# Half-H_stage.net
KiCad netlist of a schematic drawn in Altium Designer
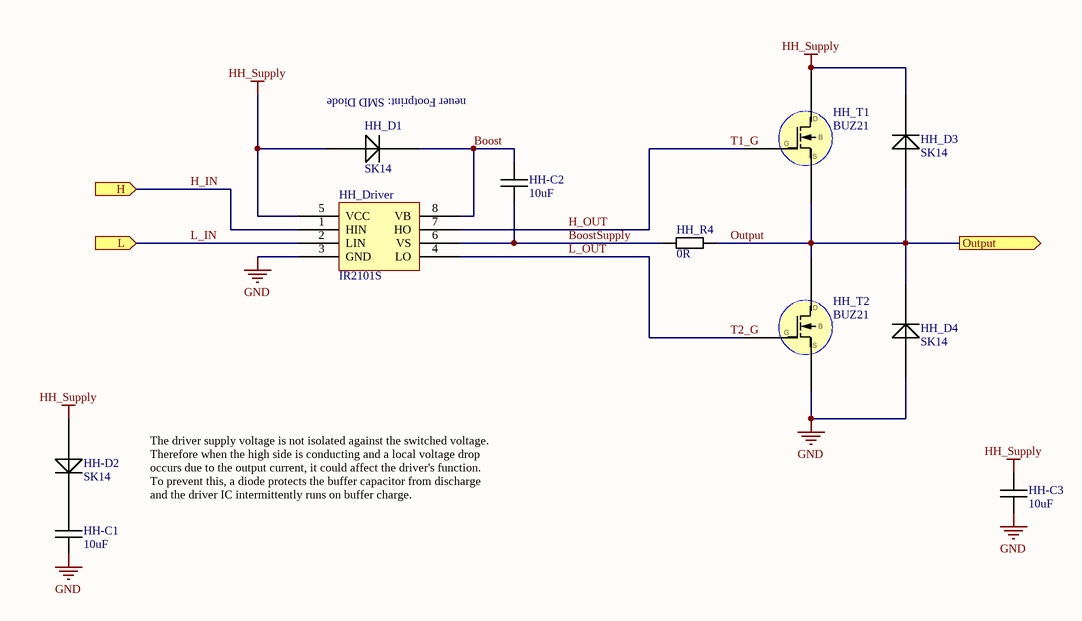
[diagram p0: Half-H stage.SchDoc]

(export (version "E")
  (design (tool "Eeschema 10.0.6"))
  (components
    (comp (ref "HH-C1")
      (value "10uF")
      (footprint "C 0805 / 2012")
      (libsource (lib "Standard") (part "Capacitor"))
    )
    (comp (ref "HH-C2")
      (value "10uF")
      (footprint "C 0805 / 2012")
      (libsource (lib "Standard") (part "Capacitor"))
    )
    (comp (ref "HH-C3")
      (value "10uF")
      (footprint "Header 1x2+1 1.0mm")
      (libsource (lib "Standard") (part "Capacitor"))
    )
    (comp (ref "HH-D2") (value "SK14") (footprint "SC-90") (libsource (lib "Standard") (part "Diode")))
    (comp (ref "HH_D1") (value "SK14") (footprint "SC-90") (libsource (lib "Standard") (part "Diode")))
    (comp (ref "HH_D3") (value "SK14") (footprint "SC-90") (libsource (lib "Standard") (part "Diode")))
    (comp (ref "HH_D4") (value "SK14") (footprint "SC-90") (libsource (lib "Standard") (part "Diode")))
    (comp (ref "HH_Driver")
      (value "IR2101S")
      (footprint "SOIC-8")
      (description "High and Low Side Driver")
      (libsource (lib "ICs") (part "IR21xx"))
    )
    (comp (ref "HH_R4")
      (value "0R")
      (footprint "R 0805 / 2012 wide")
      (libsource (lib "Standard") (part "Resistor"))
    )
    (comp (ref "HH_T1")
      (value "BUZ21")
      (footprint "TO-220 AB")
      (description "Enhancement Type")
      (libsource (lib "ICs") (part "FET N-Channel"))
    )
    (comp (ref "HH_T2")
      (value "BUZ21")
      (footprint "TO-220 AB")
      (description "Enhancement Type")
      (libsource (lib "ICs") (part "FET N-Channel"))
    )
  )
  (nets
    (net (code "1") (name "/Boost") (class "Default")
      (node (ref "HH-C2") (pin "1") (pinfunction "1_1") (pintype "passive"))
      (node (ref "HH_D1") (pin "1") (pinfunction "1_1") (pintype "passive"))
      (node (ref "HH_Driver") (pin "8") (pinfunction "VB_8") (pintype "passive"))
    )
    (net (code "2") (name "/BoostSupply") (class "Default")
      (node (ref "HH-C2") (pin "2") (pinfunction "1_2") (pintype "passive"))
      (node (ref "HH_Driver") (pin "6") (pinfunction "VS_6") (pintype "passive"))
      (node (ref "HH_R4") (pin "1") (pinfunction "1_1") (pintype "passive"))
    )
    (net (code "3") (name "/H_IN") (class "Default")
      (node (ref "HH_Driver") (pin "1") (pinfunction "HIN_1") (pintype "passive"))
    )
    (net (code "4") (name "/H_OUT") (class "Default")
      (node (ref "HH_Driver") (pin "7") (pinfunction "HO_7") (pintype "passive"))
      (node (ref "HH_T1") (pin "1") (pinfunction "1_1") (pintype "passive"))
    )
    (net (code "5") (name "/L_IN") (class "Default")
      (node (ref "HH_Driver") (pin "2") (pinfunction "LIN_2") (pintype "passive"))
    )
    (net (code "6") (name "/L_OUT") (class "Default")
      (node (ref "HH_Driver") (pin "4") (pinfunction "LO_4") (pintype "passive"))
      (node (ref "HH_T2") (pin "1") (pinfunction "1_1") (pintype "passive"))
    )
    (net (code "7") (name "/Output") (class "Default")
      (node (ref "HH_D3") (pin "2") (pinfunction "2_2") (pintype "passive"))
      (node (ref "HH_D4") (pin "1") (pinfunction "1_1") (pintype "passive"))
      (node (ref "HH_R4") (pin "2") (pinfunction "2_2") (pintype "passive"))
      (node (ref "HH_T1") (pin "3") (pinfunction "3_3") (pintype "passive"))
      (node (ref "HH_T2") (pin "2") (pinfunction "2_2") (pintype "passive"))
    )
    (net (code "8") (name "GND") (class "Default")
      (node (ref "HH-C1") (pin "2") (pinfunction "1_2") (pintype "passive"))
      (node (ref "HH-C3") (pin "2") (pinfunction "1_2") (pintype "passive"))
      (node (ref "HH_D4") (pin "2") (pinfunction "2_2") (pintype "passive"))
      (node (ref "HH_Driver") (pin "3") (pinfunction "GND_3") (pintype "passive"))
      (node (ref "HH_T2") (pin "3") (pinfunction "3_3") (pintype "passive"))
    )
    (net (code "9") (name "HH_Supply") (class "Default")
      (node (ref "HH-C3") (pin "1") (pinfunction "1_1") (pintype "passive"))
      (node (ref "HH-D2") (pin "2") (pinfunction "2_2") (pintype "passive"))
      (node (ref "HH_D1") (pin "2") (pinfunction "2_2") (pintype "passive"))
      (node (ref "HH_D3") (pin "1") (pinfunction "1_1") (pintype "passive"))
      (node (ref "HH_Driver") (pin "5") (pinfunction "VCC_5") (pintype "passive"))
      (node (ref "HH_T1") (pin "2") (pinfunction "2_2") (pintype "passive"))
    )
    (net (code "10") (name "Net-(HH-C1-Pad1)") (class "Default")
      (node (ref "HH-C1") (pin "1") (pinfunction "1_1") (pintype "passive"))
      (node (ref "HH-D2") (pin "1") (pinfunction "1_1") (pintype "passive"))
    )
  )
)
